# Interboard.net
KiCad netlist of a schematic drawn in Altium Designer
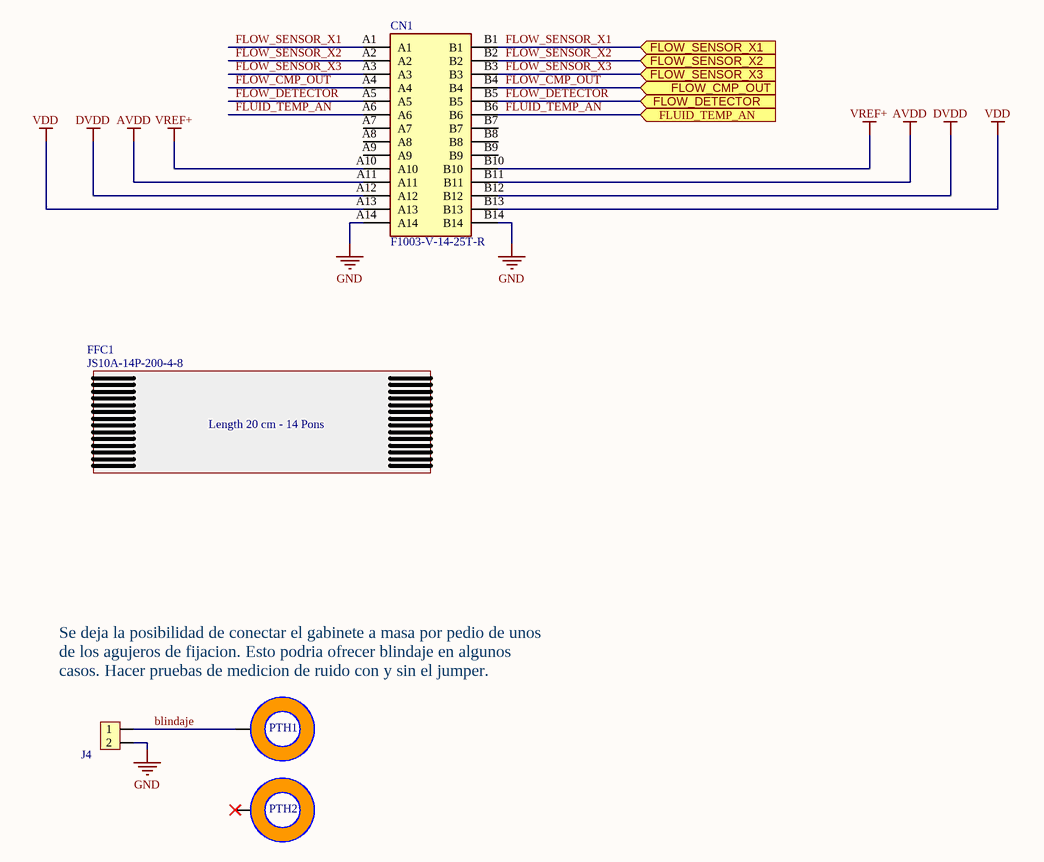
[diagram p0: Interboard.SchDoc]

(export (version "E")
  (design (tool "Eeschema 10.0.6"))
  (components
    (comp (ref "CN1")
      (value "F1003-V-14-25T-R")
      (footprint "F1003-V-14-25T-R")
      (description "14 Position FFC, FPC Connector Contacts, Vertical - 1 Sided 0.039\" (1.00mm) Surface Mount")
      (fields (field (name "MANUFACTURER") "XFCN") (field (name "VENDOR PART NUMBER") "C2764805"))
      (libsource (lib "flowmeet") (part "F1003-V-14-25T-R"))
    )
    (comp (ref "FFC1")
      (value "JS10A-14P-200-4-8")
      (footprint "no_footprint")
      (description "Length 20 cm - 14 Pons - FFC flat flexible cable")
      (fields (field (name "MANUFACTURER") "JXTCONN") (field (name "VENDOR PART NUMBER") "C2857589"))
      (libsource (lib "flowmeet") (part "JS10A-14P-200-4-8"))
    )
    (comp (ref "J4")
      (value "54101-T0600LF-CUT-2")
      (footprint "HEADER PIN 1X2")
      (description "Pin header pitch 2.54 TH - cuttable 2 od 36 positions.")
      (fields
        (field (name "MANUFACTURER") "Amphenol ICC")
        (field (name "MANUFACTURER PART NUMBER") "54101-T0600LF")
      )
      (libsource (lib "flowmeet") (part "54101-T0600LF-CUT-2"))
    )
    (comp (ref "PTH1")
      (value "PTH-3MM-L")
      (footprint "PTH_M3_L")
      (description "Montaje M3. algo de holgura y buena corona.")
      (libsource (lib "flowmeet") (part "PTH-3MM-L"))
    )
    (comp (ref "PTH2")
      (value "PTH-3MM-L")
      (footprint "PTH_M3_L")
      (description "Montaje M3. algo de holgura y buena corona.")
      (libsource (lib "flowmeet") (part "PTH-3MM-L"))
    )
  )
  (nets
    (net (code "1") (name "/FLOW_CMP_OUT") (class "Default")
      (node (ref "CN1") (pin "A4") (pinfunction "A4_A4") (pintype "passive"))
      (node (ref "CN1") (pin "B4") (pinfunction "B4_B4") (pintype "passive"))
    )
    (net (code "2") (name "/FLOW_DETECTOR") (class "Default")
      (node (ref "CN1") (pin "A5") (pinfunction "A5_A5") (pintype "passive"))
      (node (ref "CN1") (pin "B5") (pinfunction "B5_B5") (pintype "passive"))
    )
    (net (code "3") (name "/FLOW_SENSOR_X1") (class "Default")
      (node (ref "CN1") (pin "A1") (pinfunction "A1_A1") (pintype "passive"))
      (node (ref "CN1") (pin "B1") (pinfunction "B1_B1") (pintype "passive"))
    )
    (net (code "4") (name "/FLOW_SENSOR_X2") (class "Default")
      (node (ref "CN1") (pin "A2") (pinfunction "A2_A2") (pintype "passive"))
      (node (ref "CN1") (pin "B2") (pinfunction "B2_B2") (pintype "passive"))
    )
    (net (code "5") (name "/FLOW_SENSOR_X3") (class "Default")
      (node (ref "CN1") (pin "A3") (pinfunction "A3_A3") (pintype "passive"))
      (node (ref "CN1") (pin "B3") (pinfunction "B3_B3") (pintype "passive"))
    )
    (net (code "6") (name "/FLUID_TEMP_AN") (class "Default")
      (node (ref "CN1") (pin "A6") (pinfunction "A6_A6") (pintype "passive"))
      (node (ref "CN1") (pin "B6") (pinfunction "B6_B6") (pintype "passive"))
    )
    (net (code "7") (name "/blindaje") (class "Default")
      (node (ref "J4") (pin "1") (pinfunction "1_1") (pintype "passive"))
      (node (ref "PTH1") (pin "1") (pinfunction "1_1") (pintype "passive"))
    )
    (net (code "8") (name "AVDD") (class "Default")
      (node (ref "CN1") (pin "A11") (pinfunction "A11_A11") (pintype "passive"))
      (node (ref "CN1") (pin "B11") (pinfunction "B11_B11") (pintype "passive"))
    )
    (net (code "9") (name "DVDD") (class "Default")
      (node (ref "CN1") (pin "A12") (pinfunction "A12_A12") (pintype "passive"))
      (node (ref "CN1") (pin "B12") (pinfunction "B12_B12") (pintype "passive"))
    )
    (net (code "10") (name "GND") (class "Default")
      (node (ref "CN1") (pin "A14") (pinfunction "A14_A14") (pintype "passive"))
      (node (ref "CN1") (pin "B14") (pinfunction "B14_B14") (pintype "passive"))
      (node (ref "J4") (pin "2") (pinfunction "2_2") (pintype "passive"))
    )
    (net (code "11") (name "VDD") (class "Default")
      (node (ref "CN1") (pin "A13") (pinfunction "A13_A13") (pintype "passive"))
      (node (ref "CN1") (pin "B13") (pinfunction "B13_B13") (pintype "passive"))
    )
    (net (code "12") (name "VREF+") (class "Default")
      (node (ref "CN1") (pin "A10") (pinfunction "A10_A10") (pintype "passive"))
      (node (ref "CN1") (pin "B10") (pinfunction "B10_B10") (pintype "passive"))
    )
    (net (code "13") (name "unconnected-(CN1-PadA7)") (class "Default")
      (node (ref "CN1") (pin "A7") (pinfunction "A7_A7") (pintype "passive"))
    )
    (net (code "14") (name "unconnected-(CN1-PadA8)") (class "Default")
      (node (ref "CN1") (pin "A8") (pinfunction "A8_A8") (pintype "passive"))
    )
    (net (code "15") (name "unconnected-(CN1-PadA9)") (class "Default")
      (node (ref "CN1") (pin "A9") (pinfunction "A9_A9") (pintype "passive"))
    )
    (net (code "16") (name "unconnected-(CN1-PadB7)") (class "Default")
      (node (ref "CN1") (pin "B7") (pinfunction "B7_B7") (pintype "passive"))
    )
    (net (code "17") (name "unconnected-(CN1-PadB8)") (class "Default")
      (node (ref "CN1") (pin "B8") (pinfunction "B8_B8") (pintype "passive"))
    )
    (net (code "18") (name "unconnected-(CN1-PadB9)") (class "Default")
      (node (ref "CN1") (pin "B9") (pinfunction "B9_B9") (pintype "passive"))
    )
    (net (code "19") (name "unconnected-(PTH2-Pad1)") (class "Default")
      (node (ref "PTH2") (pin "1") (pinfunction "1_1") (pintype "passive+no_connect"))
    )
  )
)
